# Communication.net
KiCad netlist of a schematic drawn in Altium Designer
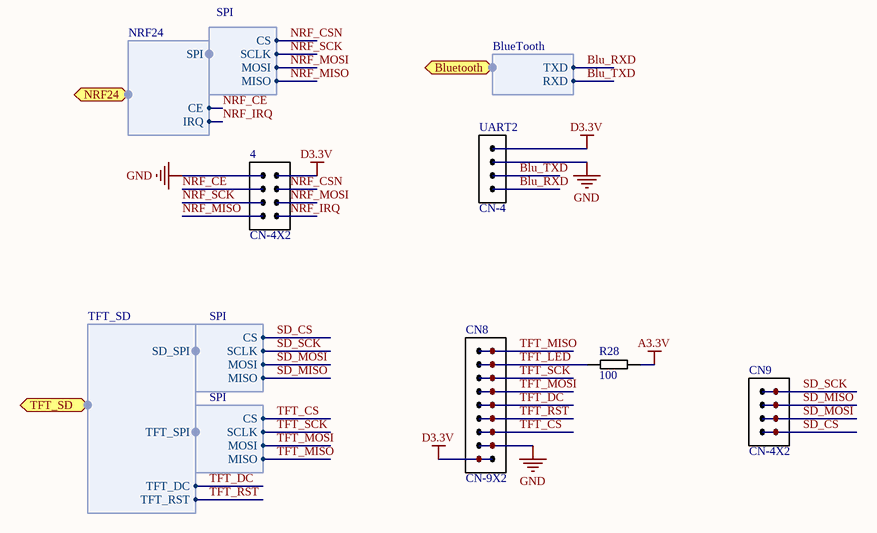
[diagram p0: Communication.SchDoc]

(export (version "E")
  (design (tool "Eeschema 10.0.6"))
  (components
    (comp (ref "4") (value "CN-4X2") (footprint "IDC-8") (libsource (lib "开关·连接器") (part "CN-4X2")))
    (comp (ref "CN8") (value "CN-9X2") (footprint "IDC-18") (libsource (lib "开关·连接器") (part "CN-9X2")))
    (comp (ref "CN9") (value "CN-4X2") (footprint "IDC-8") (libsource (lib "开关·连接器") (part "CN-4X2")))
    (comp (ref "R28")
      (value "100")
      (footprint "0805-R")
      (description "贴片")
      (libsource (lib "authuir") (part "RES_Chip"))
    )
    (comp (ref "UART2") (value "CN-4") (footprint "SIP-4") (libsource (lib "开关·连接器") (part "CN-4")))
  )
  (nets
    (net (code "4") (name "/Blu_RXD") (class "Default")
      (node (ref "UART2") (pin "4") (pinfunction "4_4") (pintype "passive"))
    )
    (net (code "5") (name "/Blu_TXD") (class "Default")
      (node (ref "UART2") (pin "3") (pinfunction "3_3") (pintype "passive"))
    )
    (net (code "6") (name "/NRF_CE") (class "Default")
      (node (ref "4") (pin "3") (pinfunction "3_3") (pintype "passive"))
    )
    (net (code "7") (name "/NRF_CSN") (class "Default")
      (node (ref "4") (pin "4") (pinfunction "4_4") (pintype "passive"))
    )
    (net (code "8") (name "/NRF_IRQ") (class "Default")
      (node (ref "4") (pin "8") (pinfunction "8_8") (pintype "passive"))
    )
    (net (code "9") (name "/NRF_MISO") (class "Default")
      (node (ref "4") (pin "7") (pinfunction "7_7") (pintype "passive"))
    )
    (net (code "10") (name "/NRF_MOSI") (class "Default")
      (node (ref "4") (pin "6") (pinfunction "6_6") (pintype "passive"))
    )
    (net (code "11") (name "/NRF_SCK") (class "Default")
      (node (ref "4") (pin "5") (pinfunction "5_5") (pintype "passive"))
    )
    (net (code "12") (name "/SD_CS") (class "Default")
      (node (ref "CN9") (pin "7") (pinfunction "7_7") (pintype "passive"))
      (node (ref "CN9") (pin "8") (pinfunction "8_8") (pintype "passive"))
    )
    (net (code "13") (name "/SD_MISO") (class "Default")
      (node (ref "CN9") (pin "3") (pinfunction "3_3") (pintype "passive"))
      (node (ref "CN9") (pin "4") (pinfunction "4_4") (pintype "passive"))
    )
    (net (code "14") (name "/SD_MOSI") (class "Default")
      (node (ref "CN9") (pin "5") (pinfunction "5_5") (pintype "passive"))
      (node (ref "CN9") (pin "6") (pinfunction "6_6") (pintype "passive"))
    )
    (net (code "15") (name "/SD_SCK") (class "Default")
      (node (ref "CN9") (pin "1") (pinfunction "1_1") (pintype "passive"))
      (node (ref "CN9") (pin "2") (pinfunction "2_2") (pintype "passive"))
    )
    (net (code "16") (name "/TFT_CS") (class "Default")
      (node (ref "CN8") (pin "13") (pinfunction "13_13") (pintype "passive"))
      (node (ref "CN8") (pin "14") (pinfunction "14_14") (pintype "passive"))
    )
    (net (code "17") (name "/TFT_DC") (class "Default")
      (node (ref "CN8") (pin "10") (pinfunction "10_10") (pintype "passive"))
      (node (ref "CN8") (pin "9") (pinfunction "9_9") (pintype "passive"))
    )
    (net (code "18") (name "/TFT_LED") (class "Default")
      (node (ref "CN8") (pin "3") (pinfunction "3_3") (pintype "passive"))
      (node (ref "CN8") (pin "4") (pinfunction "4_4") (pintype "passive"))
      (node (ref "R28") (pin "1") (pinfunction "1_1") (pintype "passive"))
    )
    (net (code "19") (name "/TFT_MISO") (class "Default")
      (node (ref "CN8") (pin "1") (pinfunction "1_1") (pintype "passive"))
      (node (ref "CN8") (pin "2") (pinfunction "2_2") (pintype "passive"))
    )
    (net (code "20") (name "/TFT_MOSI") (class "Default")
      (node (ref "CN8") (pin "7") (pinfunction "7_7") (pintype "passive"))
      (node (ref "CN8") (pin "8") (pinfunction "8_8") (pintype "passive"))
    )
    (net (code "21") (name "/TFT_RST") (class "Default")
      (node (ref "CN8") (pin "11") (pinfunction "11_11") (pintype "passive"))
      (node (ref "CN8") (pin "12") (pinfunction "12_12") (pintype "passive"))
    )
    (net (code "22") (name "/TFT_SCK") (class "Default")
      (node (ref "CN8") (pin "5") (pinfunction "5_5") (pintype "passive"))
      (node (ref "CN8") (pin "6") (pinfunction "6_6") (pintype "passive"))
    )
    (net (code "26") (name "A3.3V") (class "Default")
      (node (ref "R28") (pin "2") (pinfunction "2_2") (pintype "passive"))
    )
    (net (code "27") (name "D3.3V") (class "Default")
      (node (ref "4") (pin "2") (pinfunction "2_2") (pintype "passive"))
      (node (ref "CN8") (pin "17") (pinfunction "17_17") (pintype "passive"))
      (node (ref "CN8") (pin "18") (pinfunction "18_18") (pintype "passive"))
      (node (ref "UART2") (pin "1") (pinfunction "1_1") (pintype "passive"))
    )
    (net (code "28") (name "GND") (class "Default")
      (node (ref "4") (pin "1") (pinfunction "1_1") (pintype "passive"))
      (node (ref "CN8") (pin "15") (pinfunction "15_15") (pintype "passive"))
      (node (ref "CN8") (pin "16") (pinfunction "16_16") (pintype "passive"))
      (node (ref "UART2") (pin "2") (pinfunction "2_2") (pintype "passive"))
    )
  )
)
